# ShiftRegV1_3.net
KiCad netlist of a schematic drawn in EasyEDA
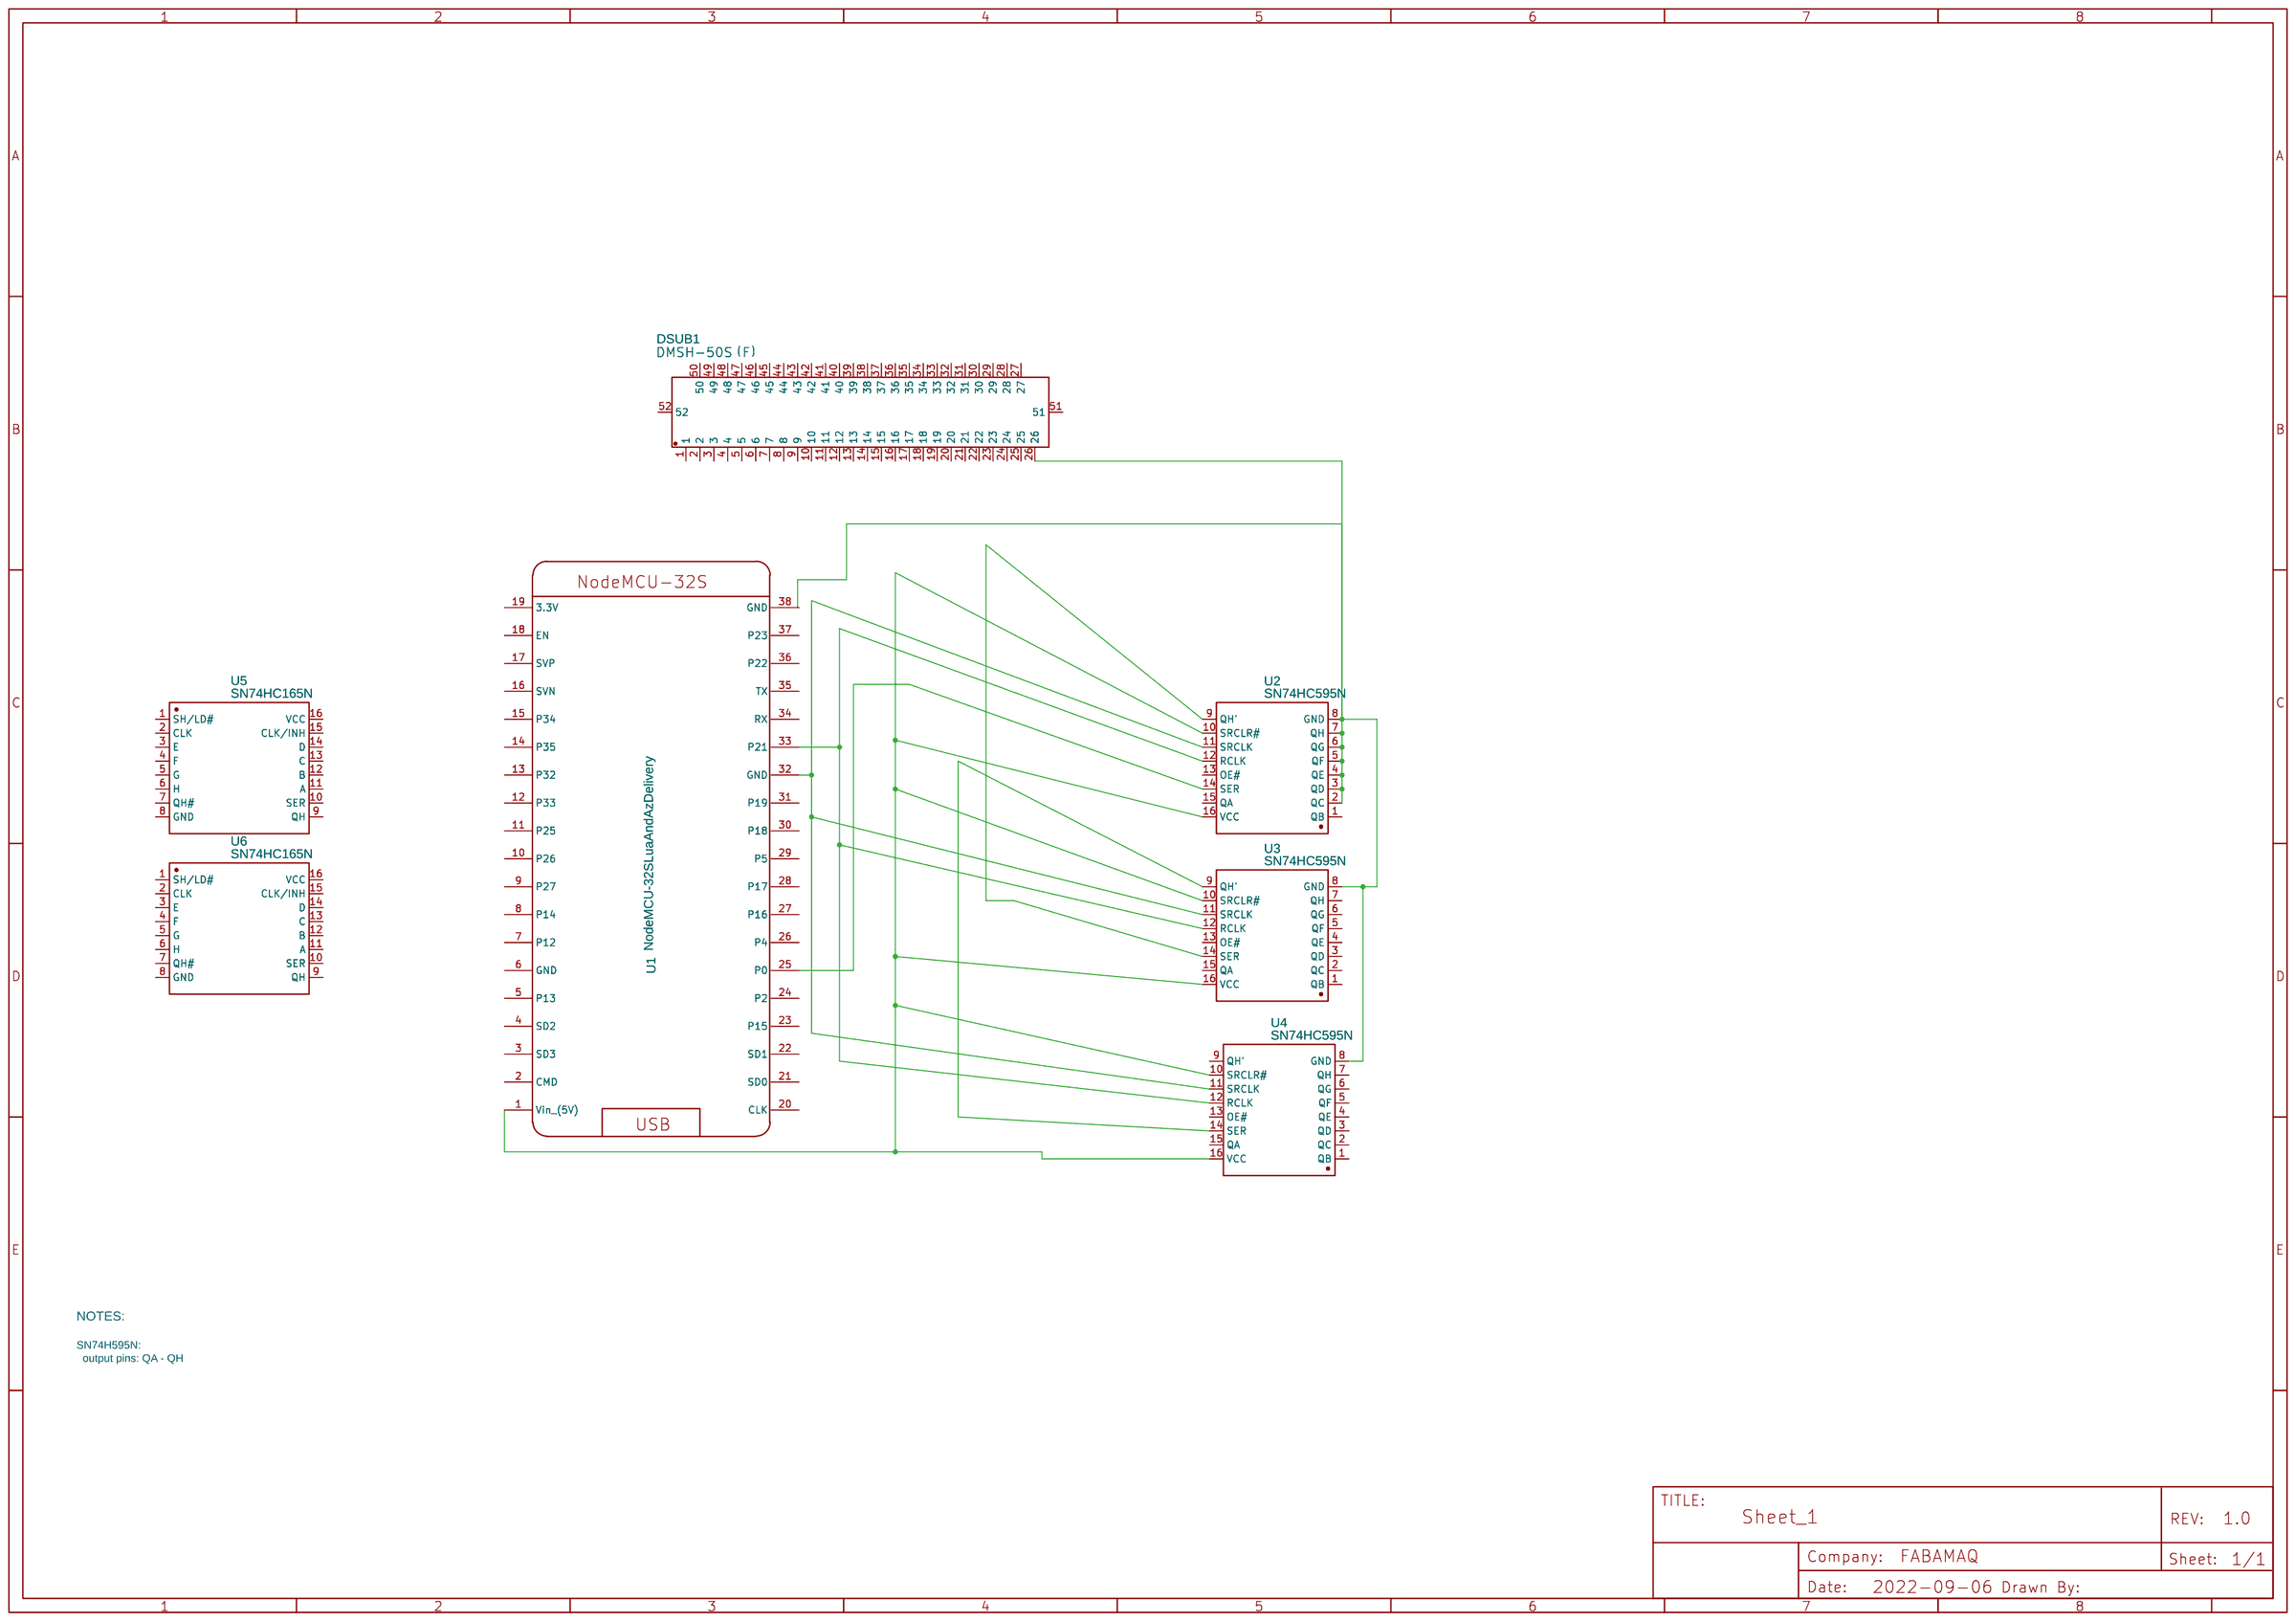
[diagram p0: schematic sheet]

(export (version "E")
  (design (tool "Eeschema 10.0.6"))
  (components
    (comp (ref "DSUB1")
      (value "DMSH-50S（F）")
      (fields (field (name "BOM_Supplier Part") "C98869"))
      (libsource (lib "") (part "DMSH-50S（F）"))
    )
    (comp (ref "U1")
      (value "NodeMCU-32SLuaAndAzDelivery")
      (fields
        (field (name "BOM_Manufacturer Part") "NodeMCU-32SLua")
        (field (name "BOM_Supplier Part") "C111436")
      )
      (libsource (lib "") (part "NodeMCU-32SLuaAndAzDelivery"))
    )
    (comp (ref "U2")
      (value "SN74HC595N")
      (fields (field (name "BOM_Supplier Part") "C78711"))
      (libsource (lib "") (part "SN74HC595N"))
    )
    (comp (ref "U3")
      (value "SN74HC595N")
      (fields (field (name "BOM_Supplier Part") "C78711"))
      (libsource (lib "") (part "SN74HC595N"))
    )
    (comp (ref "U4")
      (value "SN74HC595N")
      (fields (field (name "BOM_Supplier Part") "C78711"))
      (libsource (lib "") (part "SN74HC595N"))
    )
    (comp (ref "U5")
      (value "SN74HC165N")
      (fields (field (name "BOM_Supplier Part") "C2909"))
      (libsource (lib "") (part "SN74HC165N"))
    )
    (comp (ref "U6")
      (value "SN74HC165N")
      (fields (field (name "BOM_Supplier Part") "C2909"))
      (libsource (lib "") (part "SN74HC165N"))
    )
  )
  (nets
    (net (code "1") (name "Net-(U1-P0)") (class "Default")
      (node (ref "U1") (pin "25") (pinfunction "P0_25") (pintype "unspecified"))
      (node (ref "U2") (pin "14") (pinfunction "SER_14") (pintype "unspecified"))
    )
    (net (code "2") (name "Net-(U1-P21)") (class "Default")
      (node (ref "U1") (pin "33") (pinfunction "P21_33") (pintype "unspecified"))
      (node (ref "U2") (pin "12") (pinfunction "RCLK_12") (pintype "unspecified"))
      (node (ref "U3") (pin "12") (pinfunction "RCLK_12") (pintype "unspecified"))
      (node (ref "U4") (pin "12") (pinfunction "RCLK_12") (pintype "unspecified"))
    )
    (net (code "3") (name "Net-(U1-Vin_(5V))") (class "Default")
      (node (ref "U1") (pin "1") (pinfunction "Vin_(5V)_1") (pintype "unspecified"))
      (node (ref "U2") (pin "10") (pinfunction "SRCLR#_10") (pintype "unspecified"))
      (node (ref "U2") (pin "16") (pinfunction "VCC_16") (pintype "unspecified"))
      (node (ref "U3") (pin "10") (pinfunction "SRCLR#_10") (pintype "unspecified"))
      (node (ref "U3") (pin "16") (pinfunction "VCC_16") (pintype "unspecified"))
      (node (ref "U4") (pin "10") (pinfunction "SRCLR#_10") (pintype "unspecified"))
      (node (ref "U4") (pin "16") (pinfunction "VCC_16") (pintype "unspecified"))
    )
    (net (code "4") (name "Net-(U2-GND)") (class "Default")
      (node (ref "DSUB1") (pin "26") (pinfunction "26_26") (pintype "unspecified"))
      (node (ref "U1") (pin "38") (pinfunction "GND_38") (pintype "unspecified"))
      (node (ref "U2") (pin "2") (pinfunction "QC_2") (pintype "unspecified"))
      (node (ref "U2") (pin "3") (pinfunction "QD_3") (pintype "unspecified"))
      (node (ref "U2") (pin "4") (pinfunction "QE_4") (pintype "unspecified"))
      (node (ref "U2") (pin "5") (pinfunction "QF_5") (pintype "unspecified"))
      (node (ref "U2") (pin "6") (pinfunction "QG_6") (pintype "unspecified"))
      (node (ref "U2") (pin "7") (pinfunction "QH_7") (pintype "unspecified"))
      (node (ref "U2") (pin "8") (pinfunction "GND_8") (pintype "unspecified"))
      (node (ref "U3") (pin "8") (pinfunction "GND_8") (pintype "unspecified"))
      (node (ref "U4") (pin "8") (pinfunction "GND_8") (pintype "unspecified"))
    )
    (net (code "5") (name "Net-(U2-QH')") (class "Default")
      (node (ref "U2") (pin "9") (pinfunction "QH'_9") (pintype "unspecified"))
      (node (ref "U3") (pin "14") (pinfunction "SER_14") (pintype "unspecified"))
    )
    (net (code "6") (name "Net-(U2-SRCLK)") (class "Default")
      (node (ref "U1") (pin "32") (pinfunction "GND_32") (pintype "unspecified"))
      (node (ref "U2") (pin "11") (pinfunction "SRCLK_11") (pintype "unspecified"))
      (node (ref "U3") (pin "11") (pinfunction "SRCLK_11") (pintype "unspecified"))
      (node (ref "U4") (pin "11") (pinfunction "SRCLK_11") (pintype "unspecified"))
    )
    (net (code "7") (name "Net-(U3-QH')") (class "Default")
      (node (ref "U3") (pin "9") (pinfunction "QH'_9") (pintype "unspecified"))
      (node (ref "U4") (pin "14") (pinfunction "SER_14") (pintype "unspecified"))
    )
    (net (code "8") (name "unconnected-(DSUB1-Pad1)") (class "Default")
      (node (ref "DSUB1") (pin "1") (pinfunction "1_1") (pintype "unspecified"))
    )
    (net (code "9") (name "unconnected-(DSUB1-Pad2)") (class "Default")
      (node (ref "DSUB1") (pin "2") (pinfunction "2_2") (pintype "unspecified"))
    )
    (net (code "10") (name "unconnected-(DSUB1-Pad3)") (class "Default")
      (node (ref "DSUB1") (pin "3") (pinfunction "3_3") (pintype "unspecified"))
    )
    (net (code "11") (name "unconnected-(DSUB1-Pad4)") (class "Default")
      (node (ref "DSUB1") (pin "4") (pinfunction "4_4") (pintype "unspecified"))
    )
    (net (code "12") (name "unconnected-(DSUB1-Pad5)") (class "Default")
      (node (ref "DSUB1") (pin "5") (pinfunction "5_5") (pintype "unspecified"))
    )
    (net (code "13") (name "unconnected-(DSUB1-Pad6)") (class "Default")
      (node (ref "DSUB1") (pin "6") (pinfunction "6_6") (pintype "unspecified"))
    )
    (net (code "14") (name "unconnected-(DSUB1-Pad7)") (class "Default")
      (node (ref "DSUB1") (pin "7") (pinfunction "7_7") (pintype "unspecified"))
    )
    (net (code "15") (name "unconnected-(DSUB1-Pad8)") (class "Default")
      (node (ref "DSUB1") (pin "8") (pinfunction "8_8") (pintype "unspecified"))
    )
    (net (code "16") (name "unconnected-(DSUB1-Pad9)") (class "Default")
      (node (ref "DSUB1") (pin "9") (pinfunction "9_9") (pintype "unspecified"))
    )
    (net (code "17") (name "unconnected-(DSUB1-Pad10)") (class "Default")
      (node (ref "DSUB1") (pin "10") (pinfunction "10_10") (pintype "unspecified"))
    )
    (net (code "18") (name "unconnected-(DSUB1-Pad11)") (class "Default")
      (node (ref "DSUB1") (pin "11") (pinfunction "11_11") (pintype "unspecified"))
    )
    (net (code "19") (name "unconnected-(DSUB1-Pad12)") (class "Default")
      (node (ref "DSUB1") (pin "12") (pinfunction "12_12") (pintype "unspecified"))
    )
    (net (code "20") (name "unconnected-(DSUB1-Pad13)") (class "Default")
      (node (ref "DSUB1") (pin "13") (pinfunction "13_13") (pintype "unspecified"))
    )
    (net (code "21") (name "unconnected-(DSUB1-Pad14)") (class "Default")
      (node (ref "DSUB1") (pin "14") (pinfunction "14_14") (pintype "unspecified"))
    )
    (net (code "22") (name "unconnected-(DSUB1-Pad15)") (class "Default")
      (node (ref "DSUB1") (pin "15") (pinfunction "15_15") (pintype "unspecified"))
    )
    (net (code "23") (name "unconnected-(DSUB1-Pad16)") (class "Default")
      (node (ref "DSUB1") (pin "16") (pinfunction "16_16") (pintype "unspecified"))
    )
    (net (code "24") (name "unconnected-(DSUB1-Pad17)") (class "Default")
      (node (ref "DSUB1") (pin "17") (pinfunction "17_17") (pintype "unspecified"))
    )
    (net (code "25") (name "unconnected-(DSUB1-Pad18)") (class "Default")
      (node (ref "DSUB1") (pin "18") (pinfunction "18_18") (pintype "unspecified"))
    )
    (net (code "26") (name "unconnected-(DSUB1-Pad19)") (class "Default")
      (node (ref "DSUB1") (pin "19") (pinfunction "19_19") (pintype "unspecified"))
    )
    (net (code "27") (name "unconnected-(DSUB1-Pad20)") (class "Default")
      (node (ref "DSUB1") (pin "20") (pinfunction "20_20") (pintype "unspecified"))
    )
    (net (code "28") (name "unconnected-(DSUB1-Pad21)") (class "Default")
      (node (ref "DSUB1") (pin "21") (pinfunction "21_21") (pintype "unspecified"))
    )
    (net (code "29") (name "unconnected-(DSUB1-Pad22)") (class "Default")
      (node (ref "DSUB1") (pin "22") (pinfunction "22_22") (pintype "unspecified"))
    )
    (net (code "30") (name "unconnected-(DSUB1-Pad23)") (class "Default")
      (node (ref "DSUB1") (pin "23") (pinfunction "23_23") (pintype "unspecified"))
    )
    (net (code "31") (name "unconnected-(DSUB1-Pad24)") (class "Default")
      (node (ref "DSUB1") (pin "24") (pinfunction "24_24") (pintype "unspecified"))
    )
    (net (code "32") (name "unconnected-(DSUB1-Pad25)") (class "Default")
      (node (ref "DSUB1") (pin "25") (pinfunction "25_25") (pintype "unspecified"))
    )
    (net (code "33") (name "unconnected-(DSUB1-Pad27)") (class "Default")
      (node (ref "DSUB1") (pin "27") (pinfunction "27_27") (pintype "unspecified"))
    )
    (net (code "34") (name "unconnected-(DSUB1-Pad28)") (class "Default")
      (node (ref "DSUB1") (pin "28") (pinfunction "28_28") (pintype "unspecified"))
    )
    (net (code "35") (name "unconnected-(DSUB1-Pad29)") (class "Default")
      (node (ref "DSUB1") (pin "29") (pinfunction "29_29") (pintype "unspecified"))
    )
    (net (code "36") (name "unconnected-(DSUB1-Pad30)") (class "Default")
      (node (ref "DSUB1") (pin "30") (pinfunction "30_30") (pintype "unspecified"))
    )
    (net (code "37") (name "unconnected-(DSUB1-Pad31)") (class "Default")
      (node (ref "DSUB1") (pin "31") (pinfunction "31_31") (pintype "unspecified"))
    )
    (net (code "38") (name "unconnected-(DSUB1-Pad32)") (class "Default")
      (node (ref "DSUB1") (pin "32") (pinfunction "32_32") (pintype "unspecified"))
    )
    (net (code "39") (name "unconnected-(DSUB1-Pad33)") (class "Default")
      (node (ref "DSUB1") (pin "33") (pinfunction "33_33") (pintype "unspecified"))
    )
    (net (code "40") (name "unconnected-(DSUB1-Pad34)") (class "Default")
      (node (ref "DSUB1") (pin "34") (pinfunction "34_34") (pintype "unspecified"))
    )
    (net (code "41") (name "unconnected-(DSUB1-Pad35)") (class "Default")
      (node (ref "DSUB1") (pin "35") (pinfunction "35_35") (pintype "unspecified"))
    )
    (net (code "42") (name "unconnected-(DSUB1-Pad36)") (class "Default")
      (node (ref "DSUB1") (pin "36") (pinfunction "36_36") (pintype "unspecified"))
    )
    (net (code "43") (name "unconnected-(DSUB1-Pad37)") (class "Default")
      (node (ref "DSUB1") (pin "37") (pinfunction "37_37") (pintype "unspecified"))
    )
    (net (code "44") (name "unconnected-(DSUB1-Pad38)") (class "Default")
      (node (ref "DSUB1") (pin "38") (pinfunction "38_38") (pintype "unspecified"))
    )
    (net (code "45") (name "unconnected-(DSUB1-Pad39)") (class "Default")
      (node (ref "DSUB1") (pin "39") (pinfunction "39_39") (pintype "unspecified"))
    )
    (net (code "46") (name "unconnected-(DSUB1-Pad40)") (class "Default")
      (node (ref "DSUB1") (pin "40") (pinfunction "40_40") (pintype "unspecified"))
    )
    (net (code "47") (name "unconnected-(DSUB1-Pad41)") (class "Default")
      (node (ref "DSUB1") (pin "41") (pinfunction "41_41") (pintype "unspecified"))
    )
    (net (code "48") (name "unconnected-(DSUB1-Pad42)") (class "Default")
      (node (ref "DSUB1") (pin "42") (pinfunction "42_42") (pintype "unspecified"))
    )
    (net (code "49") (name "unconnected-(DSUB1-Pad43)") (class "Default")
      (node (ref "DSUB1") (pin "43") (pinfunction "43_43") (pintype "unspecified"))
    )
    (net (code "50") (name "unconnected-(DSUB1-Pad44)") (class "Default")
      (node (ref "DSUB1") (pin "44") (pinfunction "44_44") (pintype "unspecified"))
    )
    (net (code "51") (name "unconnected-(DSUB1-Pad45)") (class "Default")
      (node (ref "DSUB1") (pin "45") (pinfunction "45_45") (pintype "unspecified"))
    )
    (net (code "52") (name "unconnected-(DSUB1-Pad46)") (class "Default")
      (node (ref "DSUB1") (pin "46") (pinfunction "46_46") (pintype "unspecified"))
    )
    (net (code "53") (name "unconnected-(DSUB1-Pad47)") (class "Default")
      (node (ref "DSUB1") (pin "47") (pinfunction "47_47") (pintype "unspecified"))
    )
    (net (code "54") (name "unconnected-(DSUB1-Pad48)") (class "Default")
      (node (ref "DSUB1") (pin "48") (pinfunction "48_48") (pintype "unspecified"))
    )
    (net (code "55") (name "unconnected-(DSUB1-Pad49)") (class "Default")
      (node (ref "DSUB1") (pin "49") (pinfunction "49_49") (pintype "unspecified"))
    )
    (net (code "56") (name "unconnected-(DSUB1-Pad50)") (class "Default")
      (node (ref "DSUB1") (pin "50") (pinfunction "50_50") (pintype "unspecified"))
    )
    (net (code "57") (name "unconnected-(DSUB1-Pad51)") (class "Default")
      (node (ref "DSUB1") (pin "51") (pinfunction "51_51") (pintype "unspecified"))
    )
    (net (code "58") (name "unconnected-(DSUB1-Pad52)") (class "Default")
      (node (ref "DSUB1") (pin "52") (pinfunction "52_52") (pintype "unspecified"))
    )
    (net (code "59") (name "unconnected-(U1-3.3V-Pad19)") (class "Default")
      (node (ref "U1") (pin "19") (pinfunction "3.3V_19") (pintype "unspecified"))
    )
    (net (code "60") (name "unconnected-(U1-CLK-Pad20)") (class "Default")
      (node (ref "U1") (pin "20") (pinfunction "CLK_20") (pintype "unspecified"))
    )
    (net (code "61") (name "unconnected-(U1-CMD-Pad2)") (class "Default")
      (node (ref "U1") (pin "2") (pinfunction "CMD_2") (pintype "unspecified"))
    )
    (net (code "62") (name "unconnected-(U1-EN-Pad18)") (class "Default")
      (node (ref "U1") (pin "18") (pinfunction "EN_18") (pintype "unspecified"))
    )
    (net (code "63") (name "unconnected-(U1-GND-Pad6)") (class "Default")
      (node (ref "U1") (pin "6") (pinfunction "GND_6") (pintype "unspecified"))
    )
    (net (code "64") (name "unconnected-(U1-P2-Pad24)") (class "Default")
      (node (ref "U1") (pin "24") (pinfunction "P2_24") (pintype "unspecified"))
    )
    (net (code "65") (name "unconnected-(U1-P4-Pad26)") (class "Default")
      (node (ref "U1") (pin "26") (pinfunction "P4_26") (pintype "unspecified"))
    )
    (net (code "66") (name "unconnected-(U1-P5-Pad29)") (class "Default")
      (node (ref "U1") (pin "29") (pinfunction "P5_29") (pintype "unspecified"))
    )
    (net (code "67") (name "unconnected-(U1-P12-Pad7)") (class "Default")
      (node (ref "U1") (pin "7") (pinfunction "P12_7") (pintype "unspecified"))
    )
    (net (code "68") (name "unconnected-(U1-P13-Pad5)") (class "Default")
      (node (ref "U1") (pin "5") (pinfunction "P13_5") (pintype "unspecified"))
    )
    (net (code "69") (name "unconnected-(U1-P14-Pad8)") (class "Default")
      (node (ref "U1") (pin "8") (pinfunction "P14_8") (pintype "unspecified"))
    )
    (net (code "70") (name "unconnected-(U1-P15-Pad23)") (class "Default")
      (node (ref "U1") (pin "23") (pinfunction "P15_23") (pintype "unspecified"))
    )
    (net (code "71") (name "unconnected-(U1-P16-Pad27)") (class "Default")
      (node (ref "U1") (pin "27") (pinfunction "P16_27") (pintype "unspecified"))
    )
    (net (code "72") (name "unconnected-(U1-P17-Pad28)") (class "Default")
      (node (ref "U1") (pin "28") (pinfunction "P17_28") (pintype "unspecified"))
    )
    (net (code "73") (name "unconnected-(U1-P18-Pad30)") (class "Default")
      (node (ref "U1") (pin "30") (pinfunction "P18_30") (pintype "unspecified"))
    )
    (net (code "74") (name "unconnected-(U1-P19-Pad31)") (class "Default")
      (node (ref "U1") (pin "31") (pinfunction "P19_31") (pintype "unspecified"))
    )
    (net (code "75") (name "unconnected-(U1-P22-Pad36)") (class "Default")
      (node (ref "U1") (pin "36") (pinfunction "P22_36") (pintype "unspecified"))
    )
    (net (code "76") (name "unconnected-(U1-P23-Pad37)") (class "Default")
      (node (ref "U1") (pin "37") (pinfunction "P23_37") (pintype "unspecified"))
    )
    (net (code "77") (name "unconnected-(U1-P25-Pad11)") (class "Default")
      (node (ref "U1") (pin "11") (pinfunction "P25_11") (pintype "unspecified"))
    )
    (net (code "78") (name "unconnected-(U1-P26-Pad10)") (class "Default")
      (node (ref "U1") (pin "10") (pinfunction "P26_10") (pintype "unspecified"))
    )
    (net (code "79") (name "unconnected-(U1-P27-Pad9)") (class "Default")
      (node (ref "U1") (pin "9") (pinfunction "P27_9") (pintype "unspecified"))
    )
    (net (code "80") (name "unconnected-(U1-P32-Pad13)") (class "Default")
      (node (ref "U1") (pin "13") (pinfunction "P32_13") (pintype "unspecified"))
    )
    (net (code "81") (name "unconnected-(U1-P33-Pad12)") (class "Default")
      (node (ref "U1") (pin "12") (pinfunction "P33_12") (pintype "unspecified"))
    )
    (net (code "82") (name "unconnected-(U1-P34-Pad15)") (class "Default")
      (node (ref "U1") (pin "15") (pinfunction "P34_15") (pintype "unspecified"))
    )
    (net (code "83") (name "unconnected-(U1-P35-Pad14)") (class "Default")
      (node (ref "U1") (pin "14") (pinfunction "P35_14") (pintype "unspecified"))
    )
    (net (code "84") (name "unconnected-(U1-RX-Pad34)") (class "Default")
      (node (ref "U1") (pin "34") (pinfunction "RX_34") (pintype "unspecified"))
    )
    (net (code "85") (name "unconnected-(U1-SD0-Pad21)") (class "Default")
      (node (ref "U1") (pin "21") (pinfunction "SD0_21") (pintype "unspecified"))
    )
    (net (code "86") (name "unconnected-(U1-SD1-Pad22)") (class "Default")
      (node (ref "U1") (pin "22") (pinfunction "SD1_22") (pintype "unspecified"))
    )
    (net (code "87") (name "unconnected-(U1-SD2-Pad4)") (class "Default")
      (node (ref "U1") (pin "4") (pinfunction "SD2_4") (pintype "unspecified"))
    )
    (net (code "88") (name "unconnected-(U1-SD3-Pad3)") (class "Default")
      (node (ref "U1") (pin "3") (pinfunction "SD3_3") (pintype "unspecified"))
    )
    (net (code "89") (name "unconnected-(U1-SVN-Pad16)") (class "Default")
      (node (ref "U1") (pin "16") (pinfunction "SVN_16") (pintype "unspecified"))
    )
    (net (code "90") (name "unconnected-(U1-SVP-Pad17)") (class "Default")
      (node (ref "U1") (pin "17") (pinfunction "SVP_17") (pintype "unspecified"))
    )
    (net (code "91") (name "unconnected-(U1-TX-Pad35)") (class "Default")
      (node (ref "U1") (pin "35") (pinfunction "TX_35") (pintype "unspecified"))
    )
    (net (code "92") (name "unconnected-(U2-OE#-Pad13)") (class "Default")
      (node (ref "U2") (pin "13") (pinfunction "OE#_13") (pintype "unspecified"))
    )
    (net (code "93") (name "unconnected-(U2-QA-Pad15)") (class "Default")
      (node (ref "U2") (pin "15") (pinfunction "QA_15") (pintype "unspecified"))
    )
    (net (code "94") (name "unconnected-(U2-QB-Pad1)") (class "Default")
      (node (ref "U2") (pin "1") (pinfunction "QB_1") (pintype "unspecified"))
    )
    (net (code "95") (name "unconnected-(U3-OE#-Pad13)") (class "Default")
      (node (ref "U3") (pin "13") (pinfunction "OE#_13") (pintype "unspecified"))
    )
    (net (code "96") (name "unconnected-(U3-QA-Pad15)") (class "Default")
      (node (ref "U3") (pin "15") (pinfunction "QA_15") (pintype "unspecified"))
    )
    (net (code "97") (name "unconnected-(U3-QB-Pad1)") (class "Default")
      (node (ref "U3") (pin "1") (pinfunction "QB_1") (pintype "unspecified"))
    )
    (net (code "98") (name "unconnected-(U3-QC-Pad2)") (class "Default")
      (node (ref "U3") (pin "2") (pinfunction "QC_2") (pintype "unspecified"))
    )
    (net (code "99") (name "unconnected-(U3-QD-Pad3)") (class "Default")
      (node (ref "U3") (pin "3") (pinfunction "QD_3") (pintype "unspecified"))
    )
    (net (code "100") (name "unconnected-(U3-QE-Pad4)") (class "Default")
      (node (ref "U3") (pin "4") (pinfunction "QE_4") (pintype "unspecified"))
    )
    (net (code "101") (name "unconnected-(U3-QF-Pad5)") (class "Default")
      (node (ref "U3") (pin "5") (pinfunction "QF_5") (pintype "unspecified"))
    )
    (net (code "102") (name "unconnected-(U3-QG-Pad6)") (class "Default")
      (node (ref "U3") (pin "6") (pinfunction "QG_6") (pintype "unspecified"))
    )
    (net (code "103") (name "unconnected-(U3-QH-Pad7)") (class "Default")
      (node (ref "U3") (pin "7") (pinfunction "QH_7") (pintype "unspecified"))
    )
    (net (code "104") (name "unconnected-(U4-OE#-Pad13)") (class "Default")
      (node (ref "U4") (pin "13") (pinfunction "OE#_13") (pintype "unspecified"))
    )
    (net (code "105") (name "unconnected-(U4-QA-Pad15)") (class "Default")
      (node (ref "U4") (pin "15") (pinfunction "QA_15") (pintype "unspecified"))
    )
    (net (code "106") (name "unconnected-(U4-QB-Pad1)") (class "Default")
      (node (ref "U4") (pin "1") (pinfunction "QB_1") (pintype "unspecified"))
    )
    (net (code "107") (name "unconnected-(U4-QC-Pad2)") (class "Default")
      (node (ref "U4") (pin "2") (pinfunction "QC_2") (pintype "unspecified"))
    )
    (net (code "108") (name "unconnected-(U4-QD-Pad3)") (class "Default")
      (node (ref "U4") (pin "3") (pinfunction "QD_3") (pintype "unspecified"))
    )
    (net (code "109") (name "unconnected-(U4-QE-Pad4)") (class "Default")
      (node (ref "U4") (pin "4") (pinfunction "QE_4") (pintype "unspecified"))
    )
    (net (code "110") (name "unconnected-(U4-QF-Pad5)") (class "Default")
      (node (ref "U4") (pin "5") (pinfunction "QF_5") (pintype "unspecified"))
    )
    (net (code "111") (name "unconnected-(U4-QG-Pad6)") (class "Default")
      (node (ref "U4") (pin "6") (pinfunction "QG_6") (pintype "unspecified"))
    )
    (net (code "112") (name "unconnected-(U4-QH'-Pad9)") (class "Default")
      (node (ref "U4") (pin "9") (pinfunction "QH'_9") (pintype "unspecified"))
    )
    (net (code "113") (name "unconnected-(U4-QH-Pad7)") (class "Default")
      (node (ref "U4") (pin "7") (pinfunction "QH_7") (pintype "unspecified"))
    )
    (net (code "114") (name "unconnected-(U5-A-Pad11)") (class "Default")
      (node (ref "U5") (pin "11") (pinfunction "A_11") (pintype "unspecified"))
    )
    (net (code "115") (name "unconnected-(U5-B-Pad12)") (class "Default")
      (node (ref "U5") (pin "12") (pinfunction "B_12") (pintype "unspecified"))
    )
    (net (code "116") (name "unconnected-(U5-C-Pad13)") (class "Default")
      (node (ref "U5") (pin "13") (pinfunction "C_13") (pintype "unspecified"))
    )
    (net (code "117") (name "unconnected-(U5-CLK-Pad2)") (class "Default")
      (node (ref "U5") (pin "2") (pinfunction "CLK_2") (pintype "unspecified"))
    )
    (net (code "118") (name "unconnected-(U5-CLK{slash}INH-Pad15)") (class "Default")
      (node (ref "U5") (pin "15") (pinfunction "CLK/INH_15") (pintype "unspecified"))
    )
    (net (code "119") (name "unconnected-(U5-D-Pad14)") (class "Default")
      (node (ref "U5") (pin "14") (pinfunction "D_14") (pintype "unspecified"))
    )
    (net (code "120") (name "unconnected-(U5-E-Pad3)") (class "Default")
      (node (ref "U5") (pin "3") (pinfunction "E_3") (pintype "unspecified"))
    )
    (net (code "121") (name "unconnected-(U5-F-Pad4)") (class "Default")
      (node (ref "U5") (pin "4") (pinfunction "F_4") (pintype "unspecified"))
    )
    (net (code "122") (name "unconnected-(U5-G-Pad5)") (class "Default")
      (node (ref "U5") (pin "5") (pinfunction "G_5") (pintype "unspecified"))
    )
    (net (code "123") (name "unconnected-(U5-GND-Pad8)") (class "Default")
      (node (ref "U5") (pin "8") (pinfunction "GND_8") (pintype "unspecified"))
    )
    (net (code "124") (name "unconnected-(U5-H-Pad6)") (class "Default")
      (node (ref "U5") (pin "6") (pinfunction "H_6") (pintype "unspecified"))
    )
    (net (code "125") (name "unconnected-(U5-QH#-Pad7)") (class "Default")
      (node (ref "U5") (pin "7") (pinfunction "QH#_7") (pintype "unspecified"))
    )
    (net (code "126") (name "unconnected-(U5-QH-Pad9)") (class "Default")
      (node (ref "U5") (pin "9") (pinfunction "QH_9") (pintype "unspecified"))
    )
    (net (code "127") (name "unconnected-(U5-SER-Pad10)") (class "Default")
      (node (ref "U5") (pin "10") (pinfunction "SER_10") (pintype "unspecified"))
    )
    (net (code "128") (name "unconnected-(U5-SH{slash}LD#-Pad1)") (class "Default")
      (node (ref "U5") (pin "1") (pinfunction "SH/LD#_1") (pintype "unspecified"))
    )
    (net (code "129") (name "unconnected-(U5-VCC-Pad16)") (class "Default")
      (node (ref "U5") (pin "16") (pinfunction "VCC_16") (pintype "unspecified"))
    )
    (net (code "130") (name "unconnected-(U6-A-Pad11)") (class "Default")
      (node (ref "U6") (pin "11") (pinfunction "A_11") (pintype "unspecified"))
    )
    (net (code "131") (name "unconnected-(U6-B-Pad12)") (class "Default")
      (node (ref "U6") (pin "12") (pinfunction "B_12") (pintype "unspecified"))
    )
    (net (code "132") (name "unconnected-(U6-C-Pad13)") (class "Default")
      (node (ref "U6") (pin "13") (pinfunction "C_13") (pintype "unspecified"))
    )
    (net (code "133") (name "unconnected-(U6-CLK-Pad2)") (class "Default")
      (node (ref "U6") (pin "2") (pinfunction "CLK_2") (pintype "unspecified"))
    )
    (net (code "134") (name "unconnected-(U6-CLK{slash}INH-Pad15)") (class "Default")
      (node (ref "U6") (pin "15") (pinfunction "CLK/INH_15") (pintype "unspecified"))
    )
    (net (code "135") (name "unconnected-(U6-D-Pad14)") (class "Default")
      (node (ref "U6") (pin "14") (pinfunction "D_14") (pintype "unspecified"))
    )
    (net (code "136") (name "unconnected-(U6-E-Pad3)") (class "Default")
      (node (ref "U6") (pin "3") (pinfunction "E_3") (pintype "unspecified"))
    )
    (net (code "137") (name "unconnected-(U6-F-Pad4)") (class "Default")
      (node (ref "U6") (pin "4") (pinfunction "F_4") (pintype "unspecified"))
    )
    (net (code "138") (name "unconnected-(U6-G-Pad5)") (class "Default")
      (node (ref "U6") (pin "5") (pinfunction "G_5") (pintype "unspecified"))
    )
    (net (code "139") (name "unconnected-(U6-GND-Pad8)") (class "Default")
      (node (ref "U6") (pin "8") (pinfunction "GND_8") (pintype "unspecified"))
    )
    (net (code "140") (name "unconnected-(U6-H-Pad6)") (class "Default")
      (node (ref "U6") (pin "6") (pinfunction "H_6") (pintype "unspecified"))
    )
    (net (code "141") (name "unconnected-(U6-QH#-Pad7)") (class "Default")
      (node (ref "U6") (pin "7") (pinfunction "QH#_7") (pintype "unspecified"))
    )
    (net (code "142") (name "unconnected-(U6-QH-Pad9)") (class "Default")
      (node (ref "U6") (pin "9") (pinfunction "QH_9") (pintype "unspecified"))
    )
    (net (code "143") (name "unconnected-(U6-SER-Pad10)") (class "Default")
      (node (ref "U6") (pin "10") (pinfunction "SER_10") (pintype "unspecified"))
    )
    (net (code "144") (name "unconnected-(U6-SH{slash}LD#-Pad1)") (class "Default")
      (node (ref "U6") (pin "1") (pinfunction "SH/LD#_1") (pintype "unspecified"))
    )
    (net (code "145") (name "unconnected-(U6-VCC-Pad16)") (class "Default")
      (node (ref "U6") (pin "16") (pinfunction "VCC_16") (pintype "unspecified"))
    )
  )
)
